# UART.net
KiCad netlist of a schematic drawn in Altium Designer
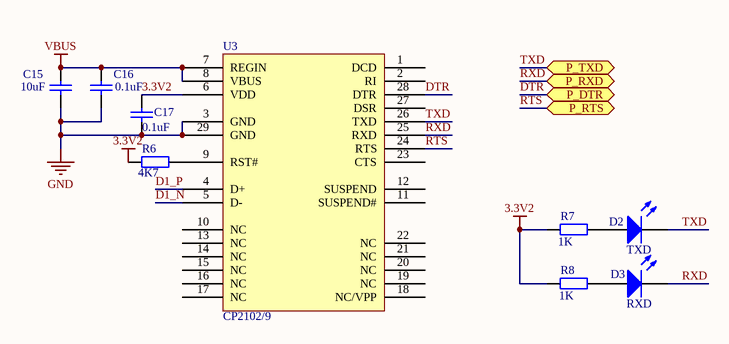
[diagram p0: UART.SchDoc]

(export (version "E")
  (design (tool "Eeschema 10.0.6"))
  (components
    (comp (ref "C15")
      (value "10uF")
      (footprint "C-0603")
      (description "Capacitor")
      (fields (field (name "Comment") "Cap") (field (name "PUBLISHER") "Altium Limited"))
      (libsource (lib "Miscellaneous Devices") (part "Cap"))
    )
    (comp (ref "C16")
      (value "0.1uF")
      (footprint "C-0603")
      (description "Capacitor")
      (fields (field (name "Comment") "Cap") (field (name "PUBLISHER") "Altium Limited"))
      (libsource (lib "Miscellaneous Devices") (part "Cap"))
    )
    (comp (ref "C17")
      (value "0.1uF")
      (footprint "C-0603")
      (description "Capacitor")
      (fields (field (name "Comment") "Cap") (field (name "PUBLISHER") "Altium Limited"))
      (libsource (lib "Miscellaneous Devices") (part "Cap"))
    )
    (comp (ref "D2")
      (value "TXD")
      (footprint "SMT_LED_0603")
      (description "Typical RED, GREEN, YELLOW, AMBER GaAs LED")
      (fields (field (name "PUBLISHER") "Altium Limited"))
      (libsource (lib "Miscellaneous Devices") (part "LED2"))
    )
    (comp (ref "D3")
      (value "RXD")
      (footprint "SMT_LED_0603")
      (description "Typical RED, GREEN, YELLOW, AMBER GaAs LED")
      (fields (field (name "PUBLISHER") "Altium Limited"))
      (libsource (lib "Miscellaneous Devices") (part "LED2"))
    )
    (comp (ref "R6")
      (value "4K7")
      (footprint "0603-1")
      (description "Resistor")
      (fields (field (name "Comment") "Res2") (field (name "PUBLISHER") "Altium Limited"))
      (libsource (lib "Miscellaneous Devices") (part "Res2"))
    )
    (comp (ref "R7")
      (value "1K")
      (footprint "0603-1")
      (description "Resistor")
      (fields (field (name "Comment") "Res2") (field (name "PUBLISHER") "Altium Limited"))
      (libsource (lib "Miscellaneous Devices") (part "Res2"))
    )
    (comp (ref "R8")
      (value "1K")
      (footprint "0603-1")
      (description "Resistor")
      (fields (field (name "Comment") "Res2") (field (name "PUBLISHER") "Altium Limited"))
      (libsource (lib "Miscellaneous Devices") (part "Res2"))
    )
    (comp (ref "U3") (value "CP2102/9") (footprint "QFN28-L") (libsource (lib "Schlib1") (part "CP2102/9")))
  )
  (nets
    (net (code "1") (name "/D1_N") (class "Default")
      (node (ref "U3") (pin "5") (pinfunction "D-_5") (pintype "passive"))
    )
    (net (code "2") (name "/D1_P") (class "Default")
      (node (ref "U3") (pin "4") (pinfunction "D+_4") (pintype "passive"))
    )
    (net (code "3") (name "/DTR") (class "Default")
      (node (ref "U3") (pin "28") (pinfunction "DTR_28") (pintype "passive"))
    )
    (net (code "4") (name "/RTS") (class "Default")
      (node (ref "U3") (pin "24") (pinfunction "RTS_24") (pintype "passive"))
    )
    (net (code "5") (name "/RXD") (class "Default")
      (node (ref "D3") (pin "2") (pinfunction "K_2") (pintype "passive"))
      (node (ref "U3") (pin "25") (pinfunction "RXD_25") (pintype "passive"))
    )
    (net (code "6") (name "/TXD") (class "Default")
      (node (ref "D2") (pin "2") (pinfunction "K_2") (pintype "passive"))
      (node (ref "U3") (pin "26") (pinfunction "TXD_26") (pintype "passive"))
    )
    (net (code "7") (name "3.3V2") (class "Default")
      (node (ref "C17") (pin "2") (pinfunction "2_2") (pintype "passive"))
      (node (ref "R6") (pin "1") (pinfunction "1_1") (pintype "passive"))
      (node (ref "R7") (pin "1") (pinfunction "1_1") (pintype "passive"))
      (node (ref "R8") (pin "1") (pinfunction "1_1") (pintype "passive"))
      (node (ref "U3") (pin "6") (pinfunction "VDD_6") (pintype "passive"))
    )
    (net (code "8") (name "GND") (class "Default")
      (node (ref "C15") (pin "1") (pinfunction "1_1") (pintype "passive"))
      (node (ref "C16") (pin "1") (pinfunction "1_1") (pintype "passive"))
      (node (ref "C17") (pin "1") (pinfunction "1_1") (pintype "passive"))
      (node (ref "U3") (pin "29") (pinfunction "GND_29") (pintype "passive"))
      (node (ref "U3") (pin "3") (pinfunction "GND_3") (pintype "passive"))
    )
    (net (code "9") (name "Net-(D2-A)") (class "Default")
      (node (ref "D2") (pin "1") (pinfunction "A_1") (pintype "passive"))
      (node (ref "R7") (pin "2") (pinfunction "2_2") (pintype "passive"))
    )
    (net (code "10") (name "Net-(D3-A)") (class "Default")
      (node (ref "D3") (pin "1") (pinfunction "A_1") (pintype "passive"))
      (node (ref "R8") (pin "2") (pinfunction "2_2") (pintype "passive"))
    )
    (net (code "11") (name "Net-(U3-RST#)") (class "Default")
      (node (ref "R6") (pin "2") (pinfunction "2_2") (pintype "passive"))
      (node (ref "U3") (pin "9") (pinfunction "RST#_9") (pintype "passive"))
    )
    (net (code "12") (name "VBUS") (class "Default")
      (node (ref "C15") (pin "2") (pinfunction "2_2") (pintype "passive"))
      (node (ref "C16") (pin "2") (pinfunction "2_2") (pintype "passive"))
      (node (ref "U3") (pin "7") (pinfunction "REGIN_7") (pintype "passive"))
      (node (ref "U3") (pin "8") (pinfunction "VBUS_8") (pintype "passive"))
    )
    (net (code "13") (name "unconnected-(U3-CTS-Pad23)") (class "Default")
      (node (ref "U3") (pin "23") (pinfunction "CTS_23") (pintype "passive"))
    )
    (net (code "14") (name "unconnected-(U3-DCD-Pad1)") (class "Default")
      (node (ref "U3") (pin "1") (pinfunction "DCD_1") (pintype "passive"))
    )
    (net (code "15") (name "unconnected-(U3-DSR-Pad27)") (class "Default")
      (node (ref "U3") (pin "27") (pinfunction "DSR_27") (pintype "passive"))
    )
    (net (code "16") (name "unconnected-(U3-NC-Pad10)") (class "Default")
      (node (ref "U3") (pin "10") (pinfunction "NC_10") (pintype "passive"))
    )
    (net (code "17") (name "unconnected-(U3-NC-Pad13)") (class "Default")
      (node (ref "U3") (pin "13") (pinfunction "NC_13") (pintype "passive"))
    )
    (net (code "18") (name "unconnected-(U3-NC-Pad14)") (class "Default")
      (node (ref "U3") (pin "14") (pinfunction "NC_14") (pintype "passive"))
    )
    (net (code "19") (name "unconnected-(U3-NC-Pad15)") (class "Default")
      (node (ref "U3") (pin "15") (pinfunction "NC_15") (pintype "passive"))
    )
    (net (code "20") (name "unconnected-(U3-NC-Pad16)") (class "Default")
      (node (ref "U3") (pin "16") (pinfunction "NC_16") (pintype "passive"))
    )
    (net (code "21") (name "unconnected-(U3-NC-Pad17)") (class "Default")
      (node (ref "U3") (pin "17") (pinfunction "NC_17") (pintype "passive"))
    )
    (net (code "22") (name "unconnected-(U3-NC-Pad19)") (class "Default")
      (node (ref "U3") (pin "19") (pinfunction "NC_19") (pintype "passive"))
    )
    (net (code "23") (name "unconnected-(U3-NC-Pad20)") (class "Default")
      (node (ref "U3") (pin "20") (pinfunction "NC_20") (pintype "passive"))
    )
    (net (code "24") (name "unconnected-(U3-NC-Pad21)") (class "Default")
      (node (ref "U3") (pin "21") (pinfunction "NC_21") (pintype "passive"))
    )
    (net (code "25") (name "unconnected-(U3-NC-Pad22)") (class "Default")
      (node (ref "U3") (pin "22") (pinfunction "NC_22") (pintype "passive"))
    )
    (net (code "26") (name "unconnected-(U3-NC{slash}VPP-Pad18)") (class "Default")
      (node (ref "U3") (pin "18") (pinfunction "NC/VPP_18") (pintype "passive"))
    )
    (net (code "27") (name "unconnected-(U3-RI-Pad2)") (class "Default")
      (node (ref "U3") (pin "2") (pinfunction "RI_2") (pintype "passive"))
    )
    (net (code "28") (name "unconnected-(U3-SUSPEND#-Pad11)") (class "Default")
      (node (ref "U3") (pin "11") (pinfunction "SUSPEND#_11") (pintype "passive"))
    )
    (net (code "29") (name "unconnected-(U3-SUSPEND-Pad12)") (class "Default")
      (node (ref "U3") (pin "12") (pinfunction "SUSPEND_12") (pintype "passive"))
    )
  )
)
